# PROC010C_XDS110_Interface_1B.net
KiCad netlist of a schematic drawn in Altium Designer
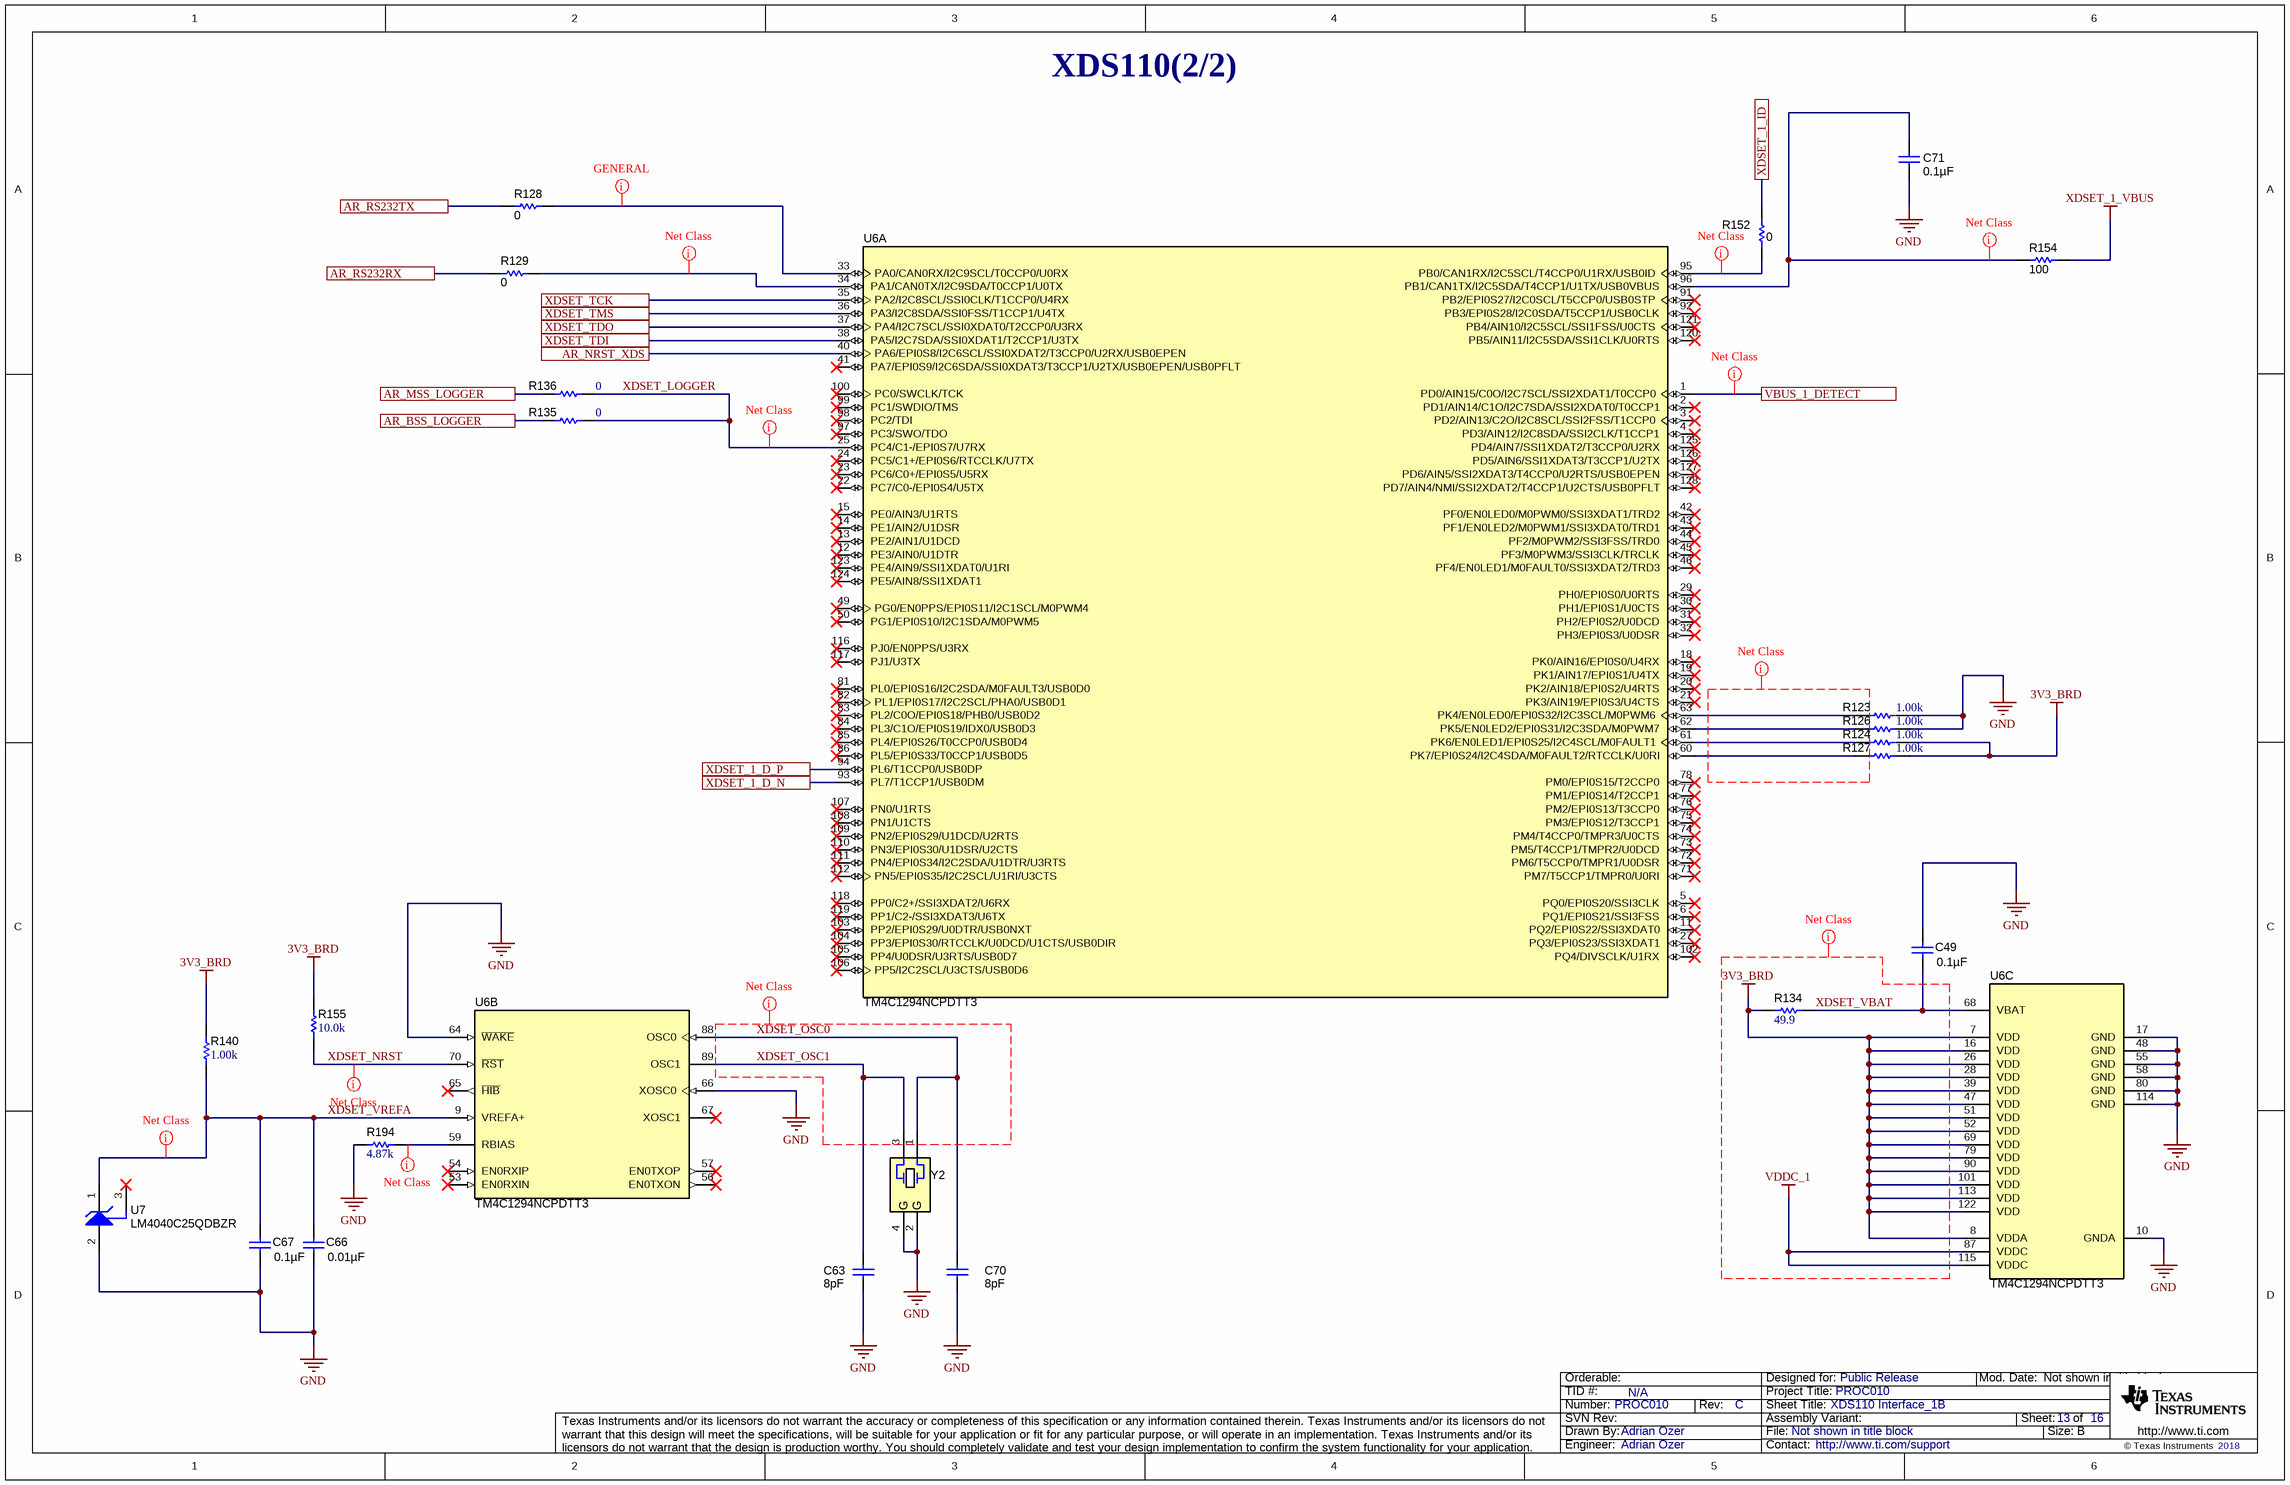
[diagram p0: PROC010C_XDS110 Interface_1B.SchDoc]

(export (version "E")
  (design (tool "Eeschema 10.0.6"))
  (components
    (comp (ref "C49")
      (value "C0402C104K8RACTU")
      (footprint "0402L")
      (description "CAP, CERM, 0.1 µF, 10 V,+/- 10%, X7R, 0402")
      (fields (field (name "MANUFACTURER") "Kemet") (field (name "VALUEDISPLAYED") "0.1µF"))
      (libsource (lib "Altium Vault - TI") (part "CMP-0078241-1"))
    )
    (comp (ref "C63")
      (value "GRM1555C1H8R0DA01D")
      (footprint "0402L")
      (description "CAP, CERM, 8 pF, 50 V, +/- 6%, C0G/NP0, 0402")
      (fields
        (field (name "MANUFACTURER") "MuRata")
        (field (name "VALUEDISPLAYED") "8pF")
        (field (name "PUBLISHER") "Texas Instruments")
      )
      (libsource (lib "Altium Vault - TI") (part "CMP-0006494-2"))
    )
    (comp (ref "C66")
      (value "C0402C103K4RACTU")
      (footprint "0402L")
      (description "CAP, CERM, 0.01 µF, 16 V,+/- 10%, X7R, 0402")
      (fields (field (name "MANUFACTURER") "Kemet") (field (name "VALUEDISPLAYED") "0.01µF"))
      (libsource (lib "Altium Vault - TI") (part "Capacitor"))
    )
    (comp (ref "C67")
      (value "C0402C104K8RACTU")
      (footprint "0402L")
      (description "CAP, CERM, 0.1 µF, 10 V,+/- 10%, X7R, 0402")
      (fields (field (name "MANUFACTURER") "Kemet") (field (name "VALUEDISPLAYED") "0.1µF"))
      (libsource (lib "Altium Vault - TI") (part "Capacitor"))
    )
    (comp (ref "C70")
      (value "GRM1555C1H8R0DA01D")
      (footprint "0402L")
      (description "CAP, CERM, 8 pF, 50 V, +/- 6%, C0G/NP0, 0402")
      (fields
        (field (name "MANUFACTURER") "MuRata")
        (field (name "VALUEDISPLAYED") "8pF")
        (field (name "PUBLISHER") "Texas Instruments")
      )
      (libsource (lib "Altium Vault - TI") (part "CMP-0006494-2"))
    )
    (comp (ref "C71")
      (value "C0402C104K8RACTU")
      (footprint "0402L")
      (description "CAP, CERM, 0.1 µF, 10 V,+/- 10%, X7R, 0402")
      (fields (field (name "MANUFACTURER") "Kemet") (field (name "VALUEDISPLAYED") "0.1µF"))
      (libsource (lib "Altium Vault - TI") (part "Capacitor"))
    )
    (comp (ref "R123")
      (value "CRCW04021K00FKED")
      (footprint "0402L")
      (description "RES, 1.00 k, 1%, 0.063 W, AEC-Q200 Grade 0, 0402")
      (fields (field (name "MANUFACTURER") "Vishay-Dale") (field (name "VALUEDISPLAYED") "1.00k"))
      (libsource (lib "Altium Vault - TI") (part "Resistor"))
    )
    (comp (ref "R124")
      (value "CRCW04021K00FKED")
      (footprint "0402L")
      (description "RES, 1.00 k, 1%, 0.063 W, AEC-Q200 Grade 0, 0402")
      (fields (field (name "MANUFACTURER") "Vishay-Dale") (field (name "VALUEDISPLAYED") "1.00k"))
      (libsource (lib "Altium Vault - TI") (part "Resistor"))
    )
    (comp (ref "R126")
      (value "CRCW04021K00FKED")
      (footprint "0402L")
      (description "RES, 1.00 k, 1%, 0.063 W, AEC-Q200 Grade 0, 0402")
      (fields (field (name "MANUFACTURER") "Vishay-Dale") (field (name "VALUEDISPLAYED") "1.00k"))
      (libsource (lib "Altium Vault - TI") (part "Resistor"))
    )
    (comp (ref "R127")
      (value "CRCW04021K00FKED")
      (footprint "0402L")
      (description "RES, 1.00 k, 1%, 0.063 W, AEC-Q200 Grade 0, 0402")
      (fields (field (name "MANUFACTURER") "Vishay-Dale") (field (name "VALUEDISPLAYED") "1.00k"))
      (libsource (lib "Altium Vault - TI") (part "Resistor"))
    )
    (comp (ref "R128")
      (value "ERJ-2GE0R00X")
      (footprint "0402L")
      (description "RES, 0, 5%, 0.063 W, 0402")
      (fields
        (field (name "MANUFACTURER") "Panasonic")
        (field (name "VALUEDISPLAYED") "0")
        (field (name "PUBLISHER") "Texas Instruments")
      )
      (libsource (lib "Altium Vault - TI") (part "Resistor"))
    )
    (comp (ref "R129")
      (value "ERJ-2GE0R00X")
      (footprint "0402L")
      (description "RES, 0, 5%, 0.063 W, 0402")
      (fields
        (field (name "MANUFACTURER") "Panasonic")
        (field (name "VALUEDISPLAYED") "0")
        (field (name "PUBLISHER") "Texas Instruments")
      )
      (libsource (lib "Altium Vault - TI") (part "Resistor"))
    )
    (comp (ref "R134")
      (value "CRCW040249R9FKED")
      (footprint "0402L")
      (description "RES, 49.9, 1%, 0.063 W, AEC-Q200 Grade 0, 0402")
      (fields (field (name "MANUFACTURER") "Vishay-Dale") (field (name "VALUEDISPLAYED") "49.9"))
      (libsource (lib "Altium Vault - TI") (part "Resistor"))
    )
    (comp (ref "R135")
      (value "CRCW02010000Z0ED")
      (footprint "0201_Silk")
      (description "RES, 0, 5%, 0.05 W, 0201")
      (fields (field (name "MANUFACTURER") "Vishay-Dale") (field (name "VALUEDISPLAYED") "0"))
      (libsource (lib "Altium Vault - TI") (part "Resistor"))
    )
    (comp (ref "R136")
      (value "CRCW02010000Z0ED")
      (footprint "0201_Silk")
      (description "RES, 0, 5%, 0.05 W, 0201")
      (fields (field (name "MANUFACTURER") "Vishay-Dale") (field (name "VALUEDISPLAYED") "0"))
      (libsource (lib "Altium Vault - TI") (part "Resistor"))
    )
    (comp (ref "R140")
      (value "CRCW04021K00FKED")
      (footprint "0402L")
      (description "RES, 1.00 k, 1%, 0.063 W, AEC-Q200 Grade 0, 0402")
      (fields (field (name "MANUFACTURER") "Vishay-Dale") (field (name "VALUEDISPLAYED") "1.00k"))
      (libsource (lib "Altium Vault - TI") (part "Resistor"))
    )
    (comp (ref "R152")
      (value "ERJ-2GE0R00X")
      (footprint "0402L")
      (description "RES, 0, 5%, 0.063 W, 0402")
      (fields
        (field (name "MANUFACTURER") "Panasonic")
        (field (name "VALUEDISPLAYED") "0")
        (field (name "PUBLISHER") "Texas Instruments")
      )
      (libsource (lib "Altium Vault - TI") (part "Resistor"))
    )
    (comp (ref "R154")
      (value "ERJ-2GEJ101X")
      (footprint "0402L")
      (description "RES, 100, 5%, 0.1 W, AEC-Q200 Grade 0, 0402")
      (fields
        (field (name "MANUFACTURER") "Panasonic")
        (field (name "VALUEDISPLAYED") "100")
        (field (name "PUBLISHER") "Texas Instruments")
      )
      (libsource (lib "Altium Vault - TI") (part "Resistor"))
    )
    (comp (ref "R155")
      (value "CRCW040210K0FKED")
      (footprint "0402L")
      (description "RES, 10.0 k, 1%, 0.063 W, AEC-Q200 Grade 0, 0402")
      (fields (field (name "MANUFACTURER") "Vishay-Dale") (field (name "VALUEDISPLAYED") "10.0k"))
      (libsource (lib "Altium Vault - TI") (part "Resistor"))
    )
    (comp (ref "R194")
      (value "CRCW04024K87FKED")
      (footprint "0402L")
      (description "RES, 4.87 k, 1%, 0.063 W, AEC-Q200 Grade 0, 0402")
      (fields (field (name "MANUFACTURER") "Vishay-Dale") (field (name "VALUEDISPLAYED") "4.87k"))
      (libsource (lib "Altium Vault - TI") (part "Resistor"))
    )
    (comp (ref "U6")
      (value "TM4C1294NCPDTT3")
      (footprint "PDT0128A")
      (fields (field (name "PARTNUMBER") "TM4C1294NCPDTT3") (field (name "MANUFACTURER") "Texas Instruments"))
      (libsource (lib "Altium Vault - TI") (part "TI-TM4C1294NCPDT-128"))
    )
    (comp (ref "U7")
      (value "LM4040C25QDBZR")
      (footprint "DBZ0003A_N")
      (fields (field (name "MANUFACTURER") "Texas Instruments") (field (name "PARTNUMBER") "LM4040C25QDBZR"))
      (libsource (lib "Altium Vault - TI") (part "TI-LM4040C25DBZ3"))
    )
    (comp (ref "Y2")
      (value "NX3225SA-16.000M-STD-CRS-2")
      (footprint "NDK_NX3225SA")
      (description "Crystal, 16 MHz, 15 ppm, 8 pF, AEC-Q200 Grade 1, SMD")
      (fields (field (name "MANUFACTURER") "NDK"))
      (libsource (lib "Altium Vault - TI") (part "CMP-0078214-2"))
    )
  )
  (nets
    (net (code "1") (name "/AR_BSS_LOGGER") (class "Default")
      (node (ref "R135") (pin "1") (pinfunction "1_1") (pintype "passive"))
    )
    (net (code "2") (name "/AR_MSS_LOGGER") (class "Default")
      (node (ref "R136") (pin "1") (pinfunction "1_1") (pintype "passive"))
    )
    (net (code "3") (name "/AR_NRST_XDS") (class "Default")
      (node (ref "U6") (pin "40") (pinfunction "PA6/EPI0S8/I2C6SCL/SSI0XDAT2/T3CCP0/U2RX/USB0EPEN_40") (pintype "bidirectional"))
    )
    (net (code "4") (name "/AR_RS232RX") (class "Default")
      (node (ref "R129") (pin "1") (pinfunction "1_1") (pintype "passive"))
    )
    (net (code "5") (name "/AR_RS232TX") (class "Default")
      (node (ref "R128") (pin "1") (pinfunction "1_1") (pintype "passive"))
    )
    (net (code "6") (name "/VBUS_1_DETECT") (class "Default")
      (node (ref "U6") (pin "1") (pinfunction "PD0/AIN15/C0O/I2C7SCL/SSI2XDAT1/T0CCP0_1") (pintype "bidirectional"))
    )
    (net (code "7") (name "/XDSET_1_D_N") (class "Default")
      (node (ref "U6") (pin "93") (pinfunction "PL7/T1CCP1/USB0DM_93") (pintype "bidirectional"))
    )
    (net (code "8") (name "/XDSET_1_D_P") (class "Default")
      (node (ref "U6") (pin "94") (pinfunction "PL6/T1CCP0/USB0DP_94") (pintype "bidirectional"))
    )
    (net (code "9") (name "/XDSET_1_ID") (class "Default")
      (node (ref "R152") (pin "2") (pinfunction "2_2") (pintype "passive"))
    )
    (net (code "10") (name "/XDSET_LOGGER") (class "Default")
      (node (ref "R135") (pin "2") (pinfunction "2_2") (pintype "passive"))
      (node (ref "R136") (pin "2") (pinfunction "2_2") (pintype "passive"))
      (node (ref "U6") (pin "25") (pinfunction "PC4/C1-/EPI0S7/U7RX_25") (pintype "bidirectional"))
    )
    (net (code "11") (name "/XDSET_NRST") (class "Default")
      (node (ref "R155") (pin "1") (pinfunction "1_1") (pintype "passive"))
      (node (ref "U6") (pin "70") (pinfunction "~{RST}_70") (pintype "input"))
    )
    (net (code "12") (name "/XDSET_OSC0") (class "Default")
      (node (ref "C70") (pin "2") (pinfunction "2_2") (pintype "passive"))
      (node (ref "U6") (pin "88") (pinfunction "OSC0_88") (pintype "input"))
      (node (ref "Y2") (pin "1") (pinfunction "1_1") (pintype "passive"))
    )
    (net (code "13") (name "/XDSET_OSC1") (class "Default")
      (node (ref "C63") (pin "2") (pinfunction "2_2") (pintype "passive"))
      (node (ref "U6") (pin "89") (pinfunction "OSC1_89") (pintype "passive"))
      (node (ref "Y2") (pin "3") (pinfunction "3_3") (pintype "passive"))
    )
    (net (code "14") (name "/XDSET_TCK") (class "Default")
      (node (ref "U6") (pin "35") (pinfunction "PA2/I2C8SCL/SSI0CLK/T1CCP0/U4RX_35") (pintype "bidirectional"))
    )
    (net (code "15") (name "/XDSET_TDI") (class "Default")
      (node (ref "U6") (pin "38") (pinfunction "PA5/I2C7SDA/SSI0XDAT1/T2CCP1/U3TX_38") (pintype "bidirectional"))
    )
    (net (code "16") (name "/XDSET_TDO") (class "Default")
      (node (ref "U6") (pin "37") (pinfunction "PA4/I2C7SCL/SSI0XDAT0/T2CCP0/U3RX_37") (pintype "bidirectional"))
    )
    (net (code "17") (name "/XDSET_TMS") (class "Default")
      (node (ref "U6") (pin "36") (pinfunction "PA3/I2C8SDA/SSI0FSS/T1CCP1/U4TX_36") (pintype "bidirectional"))
    )
    (net (code "18") (name "/XDSET_VBAT") (class "Default")
      (node (ref "C49") (pin "2") (pinfunction "2_2") (pintype "passive"))
      (node (ref "R134") (pin "1") (pinfunction "1_1") (pintype "passive"))
      (node (ref "U6") (pin "68") (pinfunction "VBAT_68") (pintype "power_in"))
    )
    (net (code "19") (name "/XDSET_VREFA") (class "Default")
      (node (ref "C66") (pin "2") (pinfunction "2_2") (pintype "passive"))
      (node (ref "C67") (pin "2") (pinfunction "2_2") (pintype "passive"))
      (node (ref "R140") (pin "1") (pinfunction "1_1") (pintype "passive"))
      (node (ref "U6") (pin "9") (pinfunction "VREFA+_9") (pintype "input"))
      (node (ref "U7") (pin "1") (pinfunction "CATHODE_1") (pintype "passive"))
    )
    (net (code "20") (name "3V3_BRD") (class "Default")
      (node (ref "R124") (pin "2") (pinfunction "2_2") (pintype "passive"))
      (node (ref "R127") (pin "2") (pinfunction "2_2") (pintype "passive"))
      (node (ref "R134") (pin "2") (pinfunction "2_2") (pintype "passive"))
      (node (ref "R140") (pin "2") (pinfunction "2_2") (pintype "passive"))
      (node (ref "R155") (pin "2") (pinfunction "2_2") (pintype "passive"))
      (node (ref "U6") (pin "101") (pinfunction "VDD_101") (pintype "power_in"))
      (node (ref "U6") (pin "113") (pinfunction "VDD_113") (pintype "power_in"))
      (node (ref "U6") (pin "122") (pinfunction "VDD_122") (pintype "power_in"))
      (node (ref "U6") (pin "16") (pinfunction "VDD_16") (pintype "power_in"))
      (node (ref "U6") (pin "26") (pinfunction "VDD_26") (pintype "power_in"))
      (node (ref "U6") (pin "28") (pinfunction "VDD_28") (pintype "power_in"))
      (node (ref "U6") (pin "39") (pinfunction "VDD_39") (pintype "power_in"))
      (node (ref "U6") (pin "47") (pinfunction "VDD_47") (pintype "power_in"))
      (node (ref "U6") (pin "51") (pinfunction "VDD_51") (pintype "power_in"))
      (node (ref "U6") (pin "52") (pinfunction "VDD_52") (pintype "power_in"))
      (node (ref "U6") (pin "69") (pinfunction "VDD_69") (pintype "power_in"))
      (node (ref "U6") (pin "7") (pinfunction "VDD_7") (pintype "power_in"))
      (node (ref "U6") (pin "79") (pinfunction "VDD_79") (pintype "power_in"))
      (node (ref "U6") (pin "8") (pinfunction "VDDA_8") (pintype "power_in"))
      (node (ref "U6") (pin "90") (pinfunction "VDD_90") (pintype "power_in"))
    )
    (net (code "21") (name "GND") (class "Default")
      (node (ref "C49") (pin "1") (pinfunction "1_1") (pintype "passive"))
      (node (ref "C63") (pin "1") (pinfunction "1_1") (pintype "passive"))
      (node (ref "C66") (pin "1") (pinfunction "1_1") (pintype "passive"))
      (node (ref "C67") (pin "1") (pinfunction "1_1") (pintype "passive"))
      (node (ref "C70") (pin "1") (pinfunction "1_1") (pintype "passive"))
      (node (ref "C71") (pin "1") (pinfunction "1_1") (pintype "passive"))
      (node (ref "R123") (pin "2") (pinfunction "2_2") (pintype "passive"))
      (node (ref "R126") (pin "2") (pinfunction "2_2") (pintype "passive"))
      (node (ref "R194") (pin "1") (pinfunction "1_1") (pintype "passive"))
      (node (ref "U6") (pin "10") (pinfunction "GNDA_10") (pintype "power_in"))
      (node (ref "U6") (pin "114") (pinfunction "GND_114") (pintype "power_in"))
      (node (ref "U6") (pin "17") (pinfunction "GND_17") (pintype "power_in"))
      (node (ref "U6") (pin "48") (pinfunction "GND_48") (pintype "power_in"))
      (node (ref "U6") (pin "55") (pinfunction "GND_55") (pintype "power_in"))
      (node (ref "U6") (pin "58") (pinfunction "GND_58") (pintype "power_in"))
      (node (ref "U6") (pin "64") (pinfunction "~{WAKE}_64") (pintype "input"))
      (node (ref "U6") (pin "66") (pinfunction "XOSC0_66") (pintype "input"))
      (node (ref "U6") (pin "80") (pinfunction "GND_80") (pintype "power_in"))
      (node (ref "U7") (pin "2") (pinfunction "ANODE_2") (pintype "passive"))
      (node (ref "Y2") (pin "2") (pinfunction "GND_2") (pintype "power_in"))
      (node (ref "Y2") (pin "4") (pinfunction "GND_4") (pintype "power_in"))
    )
    (net (code "22") (name "Net-(U6A-PA0{slash}CAN0RX{slash}I2C9SCL{slash}T0CCP0{slash}U0RX)") (class "Default")
      (node (ref "R128") (pin "2") (pinfunction "2_2") (pintype "passive"))
      (node (ref "U6") (pin "33") (pinfunction "PA0/CAN0RX/I2C9SCL/T0CCP0/U0RX_33") (pintype "bidirectional"))
    )
    (net (code "23") (name "Net-(U6A-PA1{slash}CAN0TX{slash}I2C9SDA{slash}T0CCP1{slash}U0TX)") (class "Default")
      (node (ref "R129") (pin "2") (pinfunction "2_2") (pintype "passive"))
      (node (ref "U6") (pin "34") (pinfunction "PA1/CAN0TX/I2C9SDA/T0CCP1/U0TX_34") (pintype "bidirectional"))
    )
    (net (code "24") (name "Net-(U6A-PB0{slash}CAN1RX{slash}I2C5SCL{slash}T4CCP0{slash}U1RX{slash}USB0ID)") (class "Default")
      (node (ref "R152") (pin "1") (pinfunction "1_1") (pintype "passive"))
      (node (ref "U6") (pin "95") (pinfunction "PB0/CAN1RX/I2C5SCL/T4CCP0/U1RX/USB0ID_95") (pintype "bidirectional"))
    )
    (net (code "25") (name "Net-(U6A-PB1{slash}CAN1TX{slash}I2C5SDA{slash}T4CCP1{slash}U1TX{slash}USB0VBUS)") (class "Default")
      (node (ref "C71") (pin "2") (pinfunction "2_2") (pintype "passive"))
      (node (ref "R154") (pin "1") (pinfunction "1_1") (pintype "passive"))
      (node (ref "U6") (pin "96") (pinfunction "PB1/CAN1TX/I2C5SDA/T4CCP1/U1TX/USB0VBUS_96") (pintype "bidirectional"))
    )
    (net (code "26") (name "Net-(U6A-PK4{slash}EN0LED0{slash}EPI0S32{slash}I2C3SCL{slash}M0PWM6)") (class "Default")
      (node (ref "R123") (pin "1") (pinfunction "1_1") (pintype "passive"))
      (node (ref "U6") (pin "63") (pinfunction "PK4/EN0LED0/EPI0S32/I2C3SCL/M0PWM6_63") (pintype "bidirectional"))
    )
    (net (code "27") (name "Net-(U6A-PK5{slash}EN0LED2{slash}EPI0S31{slash}I2C3SDA{slash}M0PWM7)") (class "Default")
      (node (ref "R126") (pin "1") (pinfunction "1_1") (pintype "passive"))
      (node (ref "U6") (pin "62") (pinfunction "PK5/EN0LED2/EPI0S31/I2C3SDA/M0PWM7_62") (pintype "bidirectional"))
    )
    (net (code "28") (name "Net-(U6A-PK6{slash}EN0LED1{slash}EPI0S25{slash}I2C4SCL{slash}M0FAULT1)") (class "Default")
      (node (ref "R124") (pin "1") (pinfunction "1_1") (pintype "passive"))
      (node (ref "U6") (pin "61") (pinfunction "PK6/EN0LED1/EPI0S25/I2C4SCL/M0FAULT1_61") (pintype "bidirectional"))
    )
    (net (code "29") (name "Net-(U6A-PK7{slash}EPI0S24{slash}I2C4SDA{slash}M0FAULT2{slash}RTCCLK{slash}U0RI)") (class "Default")
      (node (ref "R127") (pin "1") (pinfunction "1_1") (pintype "passive"))
      (node (ref "U6") (pin "60") (pinfunction "PK7/EPI0S24/I2C4SDA/M0FAULT2/RTCCLK/U0RI_60") (pintype "bidirectional"))
    )
    (net (code "30") (name "Net-(U6B-RBIAS)") (class "Default")
      (node (ref "R194") (pin "2") (pinfunction "2_2") (pintype "passive"))
      (node (ref "U6") (pin "59") (pinfunction "RBIAS_59") (pintype "passive"))
    )
    (net (code "31") (name "VDDC_1") (class "Default")
      (node (ref "U6") (pin "115") (pinfunction "VDDC_115") (pintype "power_in"))
      (node (ref "U6") (pin "87") (pinfunction "VDDC_87") (pintype "power_in"))
    )
    (net (code "32") (name "XDSET_1_VBUS") (class "Default")
      (node (ref "R154") (pin "2") (pinfunction "2_2") (pintype "passive"))
    )
    (net (code "33") (name "unconnected-(U6A-PA7{slash}EPI0S9{slash}I2C6SDA{slash}SSI0XDAT3{slash}T3CCP1{slash}U2TX{slash}USB0EPEN{slash}USB0PFLT-Pad41)") (class "Default")
      (node (ref "U6") (pin "41") (pinfunction "PA7/EPI0S9/I2C6SDA/SSI0XDAT3/T3CCP1/U2TX/USB0EPEN/USB0PFLT_41") (pintype "bidirectional+no_connect"))
    )
    (net (code "34") (name "unconnected-(U6A-PB2{slash}EPI0S27{slash}I2C0SCL{slash}T5CCP0{slash}USB0STP-Pad91)") (class "Default")
      (node (ref "U6") (pin "91") (pinfunction "PB2/EPI0S27/I2C0SCL/T5CCP0/USB0STP_91") (pintype "bidirectional+no_connect"))
    )
    (net (code "35") (name "unconnected-(U6A-PB3{slash}EPI0S28{slash}I2C0SDA{slash}T5CCP1{slash}USB0CLK-Pad92)") (class "Default")
      (node (ref "U6") (pin "92") (pinfunction "PB3/EPI0S28/I2C0SDA/T5CCP1/USB0CLK_92") (pintype "bidirectional+no_connect"))
    )
    (net (code "36") (name "unconnected-(U6A-PB4{slash}AIN10{slash}I2C5SCL{slash}SSI1FSS{slash}U0CTS-Pad121)") (class "Default")
      (node (ref "U6") (pin "121") (pinfunction "PB4/AIN10/I2C5SCL/SSI1FSS/U0CTS_121") (pintype "bidirectional+no_connect"))
    )
    (net (code "37") (name "unconnected-(U6A-PB5{slash}AIN11{slash}I2C5SDA{slash}SSI1CLK{slash}U0RTS-Pad120)") (class "Default")
      (node (ref "U6") (pin "120") (pinfunction "PB5/AIN11/I2C5SDA/SSI1CLK/U0RTS_120") (pintype "bidirectional+no_connect"))
    )
    (net (code "38") (name "unconnected-(U6A-PC0{slash}SWCLK{slash}TCK-Pad100)") (class "Default")
      (node (ref "U6") (pin "100") (pinfunction "PC0/SWCLK/TCK_100") (pintype "bidirectional+no_connect"))
    )
    (net (code "39") (name "unconnected-(U6A-PC1{slash}SWDIO{slash}TMS-Pad99)") (class "Default")
      (node (ref "U6") (pin "99") (pinfunction "PC1/SWDIO/TMS_99") (pintype "bidirectional+no_connect"))
    )
    (net (code "40") (name "unconnected-(U6A-PC2{slash}TDI-Pad98)") (class "Default")
      (node (ref "U6") (pin "98") (pinfunction "PC2/TDI_98") (pintype "bidirectional+no_connect"))
    )
    (net (code "41") (name "unconnected-(U6A-PC3{slash}SWO{slash}TDO-Pad97)") (class "Default")
      (node (ref "U6") (pin "97") (pinfunction "PC3/SWO/TDO_97") (pintype "bidirectional+no_connect"))
    )
    (net (code "42") (name "unconnected-(U6A-PC5{slash}C1+{slash}EPI0S6{slash}RTCCLK{slash}U7TX-Pad24)") (class "Default")
      (node (ref "U6") (pin "24") (pinfunction "PC5/C1+/EPI0S6/RTCCLK/U7TX_24") (pintype "bidirectional+no_connect"))
    )
    (net (code "43") (name "unconnected-(U6A-PC6{slash}C0+{slash}EPI0S5{slash}U5RX-Pad23)") (class "Default")
      (node (ref "U6") (pin "23") (pinfunction "PC6/C0+/EPI0S5/U5RX_23") (pintype "bidirectional+no_connect"))
    )
    (net (code "44") (name "unconnected-(U6A-PC7{slash}C0-{slash}EPI0S4{slash}U5TX-Pad22)") (class "Default")
      (node (ref "U6") (pin "22") (pinfunction "PC7/C0-/EPI0S4/U5TX_22") (pintype "bidirectional+no_connect"))
    )
    (net (code "45") (name "unconnected-(U6A-PD1{slash}AIN14{slash}C1O{slash}I2C7SDA{slash}SSI2XDAT0{slash}T0CCP1-Pad2)") (class "Default")
      (node (ref "U6") (pin "2") (pinfunction "PD1/AIN14/C1O/I2C7SDA/SSI2XDAT0/T0CCP1_2") (pintype "bidirectional+no_connect"))
    )
    (net (code "46") (name "unconnected-(U6A-PD2{slash}AIN13{slash}C2O{slash}I2C8SCL{slash}SSI2FSS{slash}T1CCP0-Pad3)") (class "Default")
      (node (ref "U6") (pin "3") (pinfunction "PD2/AIN13/C2O/I2C8SCL/SSI2FSS/T1CCP0_3") (pintype "bidirectional+no_connect"))
    )
    (net (code "47") (name "unconnected-(U6A-PD3{slash}AIN12{slash}I2C8SDA{slash}SSI2CLK{slash}T1CCP1-Pad4)") (class "Default")
      (node (ref "U6") (pin "4") (pinfunction "PD3/AIN12/I2C8SDA/SSI2CLK/T1CCP1_4") (pintype "bidirectional+no_connect"))
    )
    (net (code "48") (name "unconnected-(U6A-PD4{slash}AIN7{slash}SSI1XDAT2{slash}T3CCP0{slash}U2RX-Pad125)") (class "Default")
      (node (ref "U6") (pin "125") (pinfunction "PD4/AIN7/SSI1XDAT2/T3CCP0/U2RX_125") (pintype "bidirectional+no_connect"))
    )
    (net (code "49") (name "unconnected-(U6A-PD5{slash}AIN6{slash}SSI1XDAT3{slash}T3CCP1{slash}U2TX-Pad126)") (class "Default")
      (node (ref "U6") (pin "126") (pinfunction "PD5/AIN6/SSI1XDAT3/T3CCP1/U2TX_126") (pintype "bidirectional+no_connect"))
    )
    (net (code "50") (name "unconnected-(U6A-PD6{slash}AIN5{slash}SSI2XDAT3{slash}T4CCP0{slash}U2RTS{slash}USB0EPEN-Pad127)") (class "Default")
      (node (ref "U6") (pin "127") (pinfunction "PD6/AIN5/SSI2XDAT3/T4CCP0/U2RTS/USB0EPEN_127") (pintype "bidirectional+no_connect"))
    )
    (net (code "51") (name "unconnected-(U6A-PD7{slash}AIN4{slash}NMI{slash}SSI2XDAT2{slash}T4CCP1{slash}U2CTS{slash}USB0PFLT-Pad128)") (class "Default")
      (node (ref "U6") (pin "128") (pinfunction "PD7/AIN4/NMI/SSI2XDAT2/T4CCP1/U2CTS/USB0PFLT_128") (pintype "bidirectional+no_connect"))
    )
    (net (code "52") (name "unconnected-(U6A-PE0{slash}AIN3{slash}U1RTS-Pad15)") (class "Default")
      (node (ref "U6") (pin "15") (pinfunction "PE0/AIN3/U1RTS_15") (pintype "bidirectional+no_connect"))
    )
    (net (code "53") (name "unconnected-(U6A-PE1{slash}AIN2{slash}U1DSR-Pad14)") (class "Default")
      (node (ref "U6") (pin "14") (pinfunction "PE1/AIN2/U1DSR_14") (pintype "bidirectional+no_connect"))
    )
    (net (code "54") (name "unconnected-(U6A-PE2{slash}AIN1{slash}U1DCD-Pad13)") (class "Default")
      (node (ref "U6") (pin "13") (pinfunction "PE2/AIN1/U1DCD_13") (pintype "bidirectional+no_connect"))
    )
    (net (code "55") (name "unconnected-(U6A-PE3{slash}AIN0{slash}U1DTR-Pad12)") (class "Default")
      (node (ref "U6") (pin "12") (pinfunction "PE3/AIN0/U1DTR_12") (pintype "bidirectional+no_connect"))
    )
    (net (code "56") (name "unconnected-(U6A-PE4{slash}AIN9{slash}SSI1XDAT0{slash}U1RI-Pad123)") (class "Default")
      (node (ref "U6") (pin "123") (pinfunction "PE4/AIN9/SSI1XDAT0/U1RI_123") (pintype "bidirectional+no_connect"))
    )
    (net (code "57") (name "unconnected-(U6A-PE5{slash}AIN8{slash}SSI1XDAT1-Pad124)") (class "Default")
      (node (ref "U6") (pin "124") (pinfunction "PE5/AIN8/SSI1XDAT1_124") (pintype "bidirectional+no_connect"))
    )
    (net (code "58") (name "unconnected-(U6A-PF0{slash}EN0LED0{slash}M0PWM0{slash}SSI3XDAT1{slash}TRD2-Pad42)") (class "Default")
      (node (ref "U6") (pin "42") (pinfunction "PF0/EN0LED0/M0PWM0/SSI3XDAT1/TRD2_42") (pintype "bidirectional+no_connect"))
    )
    (net (code "59") (name "unconnected-(U6A-PF1{slash}EN0LED2{slash}M0PWM1{slash}SSI3XDAT0{slash}TRD1-Pad43)") (class "Default")
      (node (ref "U6") (pin "43") (pinfunction "PF1/EN0LED2/M0PWM1/SSI3XDAT0/TRD1_43") (pintype "bidirectional+no_connect"))
    )
    (net (code "60") (name "unconnected-(U6A-PF2{slash}M0PWM2{slash}SSI3FSS{slash}TRD0-Pad44)") (class "Default")
      (node (ref "U6") (pin "44") (pinfunction "PF2/M0PWM2/SSI3FSS/TRD0_44") (pintype "bidirectional+no_connect"))
    )
    (net (code "61") (name "unconnected-(U6A-PF3{slash}M0PWM3{slash}SSI3CLK{slash}TRCLK-Pad45)") (class "Default")
      (node (ref "U6") (pin "45") (pinfunction "PF3/M0PWM3/SSI3CLK/TRCLK_45") (pintype "bidirectional+no_connect"))
    )
    (net (code "62") (name "unconnected-(U6A-PF4{slash}EN0LED1{slash}M0FAULT0{slash}SSI3XDAT2{slash}TRD3-Pad46)") (class "Default")
      (node (ref "U6") (pin "46") (pinfunction "PF4/EN0LED1/M0FAULT0/SSI3XDAT2/TRD3_46") (pintype "bidirectional+no_connect"))
    )
    (net (code "63") (name "unconnected-(U6A-PG0{slash}EN0PPS{slash}EPI0S11{slash}I2C1SCL{slash}M0PWM4-Pad49)") (class "Default")
      (node (ref "U6") (pin "49") (pinfunction "PG0/EN0PPS/EPI0S11/I2C1SCL/M0PWM4_49") (pintype "bidirectional+no_connect"))
    )
    (net (code "64") (name "unconnected-(U6A-PG1{slash}EPI0S10{slash}I2C1SDA{slash}M0PWM5-Pad50)") (class "Default")
      (node (ref "U6") (pin "50") (pinfunction "PG1/EPI0S10/I2C1SDA/M0PWM5_50") (pintype "bidirectional+no_connect"))
    )
    (net (code "65") (name "unconnected-(U6A-PH0{slash}EPI0S0{slash}U0RTS-Pad29)") (class "Default")
      (node (ref "U6") (pin "29") (pinfunction "PH0/EPI0S0/U0RTS_29") (pintype "bidirectional+no_connect"))
    )
    (net (code "66") (name "unconnected-(U6A-PH1{slash}EPI0S1{slash}U0CTS-Pad30)") (class "Default")
      (node (ref "U6") (pin "30") (pinfunction "PH1/EPI0S1/U0CTS_30") (pintype "bidirectional+no_connect"))
    )
    (net (code "67") (name "unconnected-(U6A-PH2{slash}EPI0S2{slash}U0DCD-Pad31)") (class "Default")
      (node (ref "U6") (pin "31") (pinfunction "PH2/EPI0S2/U0DCD_31") (pintype "bidirectional+no_connect"))
    )
    (net (code "68") (name "unconnected-(U6A-PH3{slash}EPI0S3{slash}U0DSR-Pad32)") (class "Default")
      (node (ref "U6") (pin "32") (pinfunction "PH3/EPI0S3/U0DSR_32") (pintype "bidirectional+no_connect"))
    )
    (net (code "69") (name "unconnected-(U6A-PJ0{slash}EN0PPS{slash}U3RX-Pad116)") (class "Default")
      (node (ref "U6") (pin "116") (pinfunction "PJ0/EN0PPS/U3RX_116") (pintype "bidirectional+no_connect"))
    )
    (net (code "70") (name "unconnected-(U6A-PJ1{slash}U3TX-Pad117)") (class "Default")
      (node (ref "U6") (pin "117") (pinfunction "PJ1/U3TX_117") (pintype "bidirectional+no_connect"))
    )
    (net (code "71") (name "unconnected-(U6A-PK0{slash}AIN16{slash}EPI0S0{slash}U4RX-Pad18)") (class "Default")
      (node (ref "U6") (pin "18") (pinfunction "PK0/AIN16/EPI0S0/U4RX_18") (pintype "bidirectional+no_connect"))
    )
    (net (code "72") (name "unconnected-(U6A-PK1{slash}AIN17{slash}EPI0S1{slash}U4TX-Pad19)") (class "Default")
      (node (ref "U6") (pin "19") (pinfunction "PK1/AIN17/EPI0S1/U4TX_19") (pintype "bidirectional+no_connect"))
    )
    (net (code "73") (name "unconnected-(U6A-PK2{slash}AIN18{slash}EPI0S2{slash}U4RTS-Pad20)") (class "Default")
      (node (ref "U6") (pin "20") (pinfunction "PK2/AIN18/EPI0S2/U4RTS_20") (pintype "bidirectional+no_connect"))
    )
    (net (code "74") (name "unconnected-(U6A-PK3{slash}AIN19{slash}EPI0S3{slash}U4CTS-Pad21)") (class "Default")
      (node (ref "U6") (pin "21") (pinfunction "PK3/AIN19/EPI0S3/U4CTS_21") (pintype "bidirectional+no_connect"))
    )
    (net (code "75") (name "unconnected-(U6A-PL0{slash}EPI0S16{slash}I2C2SDA{slash}M0FAULT3{slash}USB0D0-Pad81)") (class "Default")
      (node (ref "U6") (pin "81") (pinfunction "PL0/EPI0S16/I2C2SDA/M0FAULT3/USB0D0_81") (pintype "bidirectional+no_connect"))
    )
    (net (code "76") (name "unconnected-(U6A-PL1{slash}EPI0S17{slash}I2C2SCL{slash}PHA0{slash}USB0D1-Pad82)") (class "Default")
      (node (ref "U6") (pin "82") (pinfunction "PL1/EPI0S17/I2C2SCL/PHA0/USB0D1_82") (pintype "bidirectional+no_connect"))
    )
    (net (code "77") (name "unconnected-(U6A-PL2{slash}C0O{slash}EPI0S18{slash}PHB0{slash}USB0D2-Pad83)") (class "Default")
      (node (ref "U6") (pin "83") (pinfunction "PL2/C0O/EPI0S18/PHB0/USB0D2_83") (pintype "bidirectional+no_connect"))
    )
    (net (code "78") (name "unconnected-(U6A-PL3{slash}C1O{slash}EPI0S19{slash}IDX0{slash}USB0D3-Pad84)") (class "Default")
      (node (ref "U6") (pin "84") (pinfunction "PL3/C1O/EPI0S19/IDX0/USB0D3_84") (pintype "bidirectional+no_connect"))
    )
    (net (code "79") (name "unconnected-(U6A-PL4{slash}EPI0S26{slash}T0CCP0{slash}USB0D4-Pad85)") (class "Default")
      (node (ref "U6") (pin "85") (pinfunction "PL4/EPI0S26/T0CCP0/USB0D4_85") (pintype "bidirectional+no_connect"))
    )
    (net (code "80") (name "unconnected-(U6A-PL5{slash}EPI0S33{slash}T0CCP1{slash}USB0D5-Pad86)") (class "Default")
      (node (ref "U6") (pin "86") (pinfunction "PL5/EPI0S33/T0CCP1/USB0D5_86") (pintype "bidirectional+no_connect"))
    )
    (net (code "81") (name "unconnected-(U6A-PM0{slash}EPI0S15{slash}T2CCP0-Pad78)") (class "Default")
      (node (ref "U6") (pin "78") (pinfunction "PM0/EPI0S15/T2CCP0_78") (pintype "bidirectional+no_connect"))
    )
    (net (code "82") (name "unconnected-(U6A-PM1{slash}EPI0S14{slash}T2CCP1-Pad77)") (class "Default")
      (node (ref "U6") (pin "77") (pinfunction "PM1/EPI0S14/T2CCP1_77") (pintype "bidirectional+no_connect"))
    )
    (net (code "83") (name "unconnected-(U6A-PM2{slash}EPI0S13{slash}T3CCP0-Pad76)") (class "Default")
      (node (ref "U6") (pin "76") (pinfunction "PM2/EPI0S13/T3CCP0_76") (pintype "bidirectional+no_connect"))
    )
    (net (code "84") (name "unconnected-(U6A-PM3{slash}EPI0S12{slash}T3CCP1-Pad75)") (class "Default")
      (node (ref "U6") (pin "75") (pinfunction "PM3/EPI0S12/T3CCP1_75") (pintype "bidirectional+no_connect"))
    )
    (net (code "85") (name "unconnected-(U6A-PM4{slash}T4CCP0{slash}TMPR3{slash}U0CTS-Pad74)") (class "Default")
      (node (ref "U6") (pin "74") (pinfunction "PM4/T4CCP0/TMPR3/U0CTS_74") (pintype "bidirectional+no_connect"))
    )
    (net (code "86") (name "unconnected-(U6A-PM5{slash}T4CCP1{slash}TMPR2{slash}U0DCD-Pad73)") (class "Default")
      (node (ref "U6") (pin "73") (pinfunction "PM5/T4CCP1/TMPR2/U0DCD_73") (pintype "bidirectional+no_connect"))
    )
    (net (code "87") (name "unconnected-(U6A-PM6{slash}T5CCP0{slash}TMPR1{slash}U0DSR-Pad72)") (class "Default")
      (node (ref "U6") (pin "72") (pinfunction "PM6/T5CCP0/TMPR1/U0DSR_72") (pintype "bidirectional+no_connect"))
    )
    (net (code "88") (name "unconnected-(U6A-PM7{slash}T5CCP1{slash}TMPR0{slash}U0RI-Pad71)") (class "Default")
      (node (ref "U6") (pin "71") (pinfunction "PM7/T5CCP1/TMPR0/U0RI_71") (pintype "bidirectional+no_connect"))
    )
    (net (code "89") (name "unconnected-(U6A-PN0{slash}U1RTS-Pad107)") (class "Default")
      (node (ref "U6") (pin "107") (pinfunction "PN0/U1RTS_107") (pintype "bidirectional+no_connect"))
    )
    (net (code "90") (name "unconnected-(U6A-PN1{slash}U1CTS-Pad108)") (class "Default")
      (node (ref "U6") (pin "108") (pinfunction "PN1/U1CTS_108") (pintype "bidirectional+no_connect"))
    )
    (net (code "91") (name "unconnected-(U6A-PN2{slash}EPI0S29{slash}U1DCD{slash}U2RTS-Pad109)") (class "Default")
      (node (ref "U6") (pin "109") (pinfunction "PN2/EPI0S29/U1DCD/U2RTS_109") (pintype "bidirectional+no_connect"))
    )
    (net (code "92") (name "unconnected-(U6A-PN3{slash}EPI0S30{slash}U1DSR{slash}U2CTS-Pad110)") (class "Default")
      (node (ref "U6") (pin "110") (pinfunction "PN3/EPI0S30/U1DSR/U2CTS_110") (pintype "bidirectional+no_connect"))
    )
    (net (code "93") (name "unconnected-(U6A-PN4{slash}EPI0S34{slash}I2C2SDA{slash}U1DTR{slash}U3RTS-Pad111)") (class "Default")
      (node (ref "U6") (pin "111") (pinfunction "PN4/EPI0S34/I2C2SDA/U1DTR/U3RTS_111") (pintype "bidirectional+no_connect"))
    )
    (net (code "94") (name "unconnected-(U6A-PN5{slash}EPI0S35{slash}I2C2SCL{slash}U1RI{slash}U3CTS-Pad112)") (class "Default")
      (node (ref "U6") (pin "112") (pinfunction "PN5/EPI0S35/I2C2SCL/U1RI/U3CTS_112") (pintype "bidirectional+no_connect"))
    )
    (net (code "95") (name "unconnected-(U6A-PP0{slash}C2+{slash}SSI3XDAT2{slash}U6RX-Pad118)") (class "Default")
      (node (ref "U6") (pin "118") (pinfunction "PP0/C2+/SSI3XDAT2/U6RX_118") (pintype "bidirectional+no_connect"))
    )
    (net (code "96") (name "unconnected-(U6A-PP1{slash}C2-{slash}SSI3XDAT3{slash}U6TX-Pad119)") (class "Default")
      (node (ref "U6") (pin "119") (pinfunction "PP1/C2-/SSI3XDAT3/U6TX_119") (pintype "bidirectional+no_connect"))
    )
    (net (code "97") (name "unconnected-(U6A-PP2{slash}EPI0S29{slash}U0DTR{slash}USB0NXT-Pad103)") (class "Default")
      (node (ref "U6") (pin "103") (pinfunction "PP2/EPI0S29/U0DTR/USB0NXT_103") (pintype "bidirectional+no_connect"))
    )
    (net (code "98") (name "unconnected-(U6A-PP3{slash}EPI0S30{slash}RTCCLK{slash}U0DCD{slash}U1CTS{slash}USB0DIR-Pad104)") (class "Default")
      (node (ref "U6") (pin "104") (pinfunction "PP3/EPI0S30/RTCCLK/U0DCD/U1CTS/USB0DIR_104") (pintype "bidirectional+no_connect"))
    )
    (net (code "99") (name "unconnected-(U6A-PP4{slash}U0DSR{slash}U3RTS{slash}USB0D7-Pad105)") (class "Default")
      (node (ref "U6") (pin "105") (pinfunction "PP4/U0DSR/U3RTS/USB0D7_105") (pintype "bidirectional+no_connect"))
    )
    (net (code "100") (name "unconnected-(U6A-PP5{slash}I2C2SCL{slash}U3CTS{slash}USB0D6-Pad106)") (class "Default")
      (node (ref "U6") (pin "106") (pinfunction "PP5/I2C2SCL/U3CTS/USB0D6_106") (pintype "bidirectional+no_connect"))
    )
    (net (code "101") (name "unconnected-(U6A-PQ0{slash}EPI0S20{slash}SSI3CLK-Pad5)") (class "Default")
      (node (ref "U6") (pin "5") (pinfunction "PQ0/EPI0S20/SSI3CLK_5") (pintype "bidirectional+no_connect"))
    )
    (net (code "102") (name "unconnected-(U6A-PQ1{slash}EPI0S21{slash}SSI3FSS-Pad6)") (class "Default")
      (node (ref "U6") (pin "6") (pinfunction "PQ1/EPI0S21/SSI3FSS_6") (pintype "bidirectional+no_connect"))
    )
    (net (code "103") (name "unconnected-(U6A-PQ2{slash}EPI0S22{slash}SSI3XDAT0-Pad11)") (class "Default")
      (node (ref "U6") (pin "11") (pinfunction "PQ2/EPI0S22/SSI3XDAT0_11") (pintype "bidirectional+no_connect"))
    )
    (net (code "104") (name "unconnected-(U6A-PQ3{slash}EPI0S23{slash}SSI3XDAT1-Pad27)") (class "Default")
      (node (ref "U6") (pin "27") (pinfunction "PQ3/EPI0S23/SSI3XDAT1_27") (pintype "bidirectional+no_connect"))
    )
    (net (code "105") (name "unconnected-(U6A-PQ4{slash}DIVSCLK{slash}U1RX-Pad102)") (class "Default")
      (node (ref "U6") (pin "102") (pinfunction "PQ4/DIVSCLK/U1RX_102") (pintype "bidirectional+no_connect"))
    )
    (net (code "106") (name "unconnected-(U6B-EN0RXIN-Pad53)") (class "Default")
      (node (ref "U6") (pin "53") (pinfunction "EN0RXIN_53") (pintype "input+no_connect"))
    )
    (net (code "107") (name "unconnected-(U6B-EN0RXIP-Pad54)") (class "Default")
      (node (ref "U6") (pin "54") (pinfunction "EN0RXIP_54") (pintype "input+no_connect"))
    )
    (net (code "108") (name "unconnected-(U6B-EN0TXON-Pad56)") (class "Default")
      (node (ref "U6") (pin "56") (pinfunction "EN0TXON_56") (pintype "output+no_connect"))
    )
    (net (code "109") (name "unconnected-(U6B-EN0TXOP-Pad57)") (class "Default")
      (node (ref "U6") (pin "57") (pinfunction "EN0TXOP_57") (pintype "output+no_connect"))
    )
    (net (code "110") (name "unconnected-(U6B-XOSC1-Pad67)") (class "Default")
      (node (ref "U6") (pin "67") (pinfunction "XOSC1_67") (pintype "passive+no_connect"))
    )
    (net (code "111") (name "unconnected-(U6B-~{HIB}-Pad65)") (class "Default")
      (node (ref "U6") (pin "65") (pinfunction "~{HIB}_65") (pintype "output+no_connect"))
    )
    (net (code "112") (name "unconnected-(U7-NC-Pad3)") (class "Default")
      (node (ref "U7") (pin "3") (pinfunction "NC_3") (pintype "passive+no_connect"))
    )
  )
)
